# LTC_Reader_V2.net
KiCad netlist of a schematic drawn in EAGLE
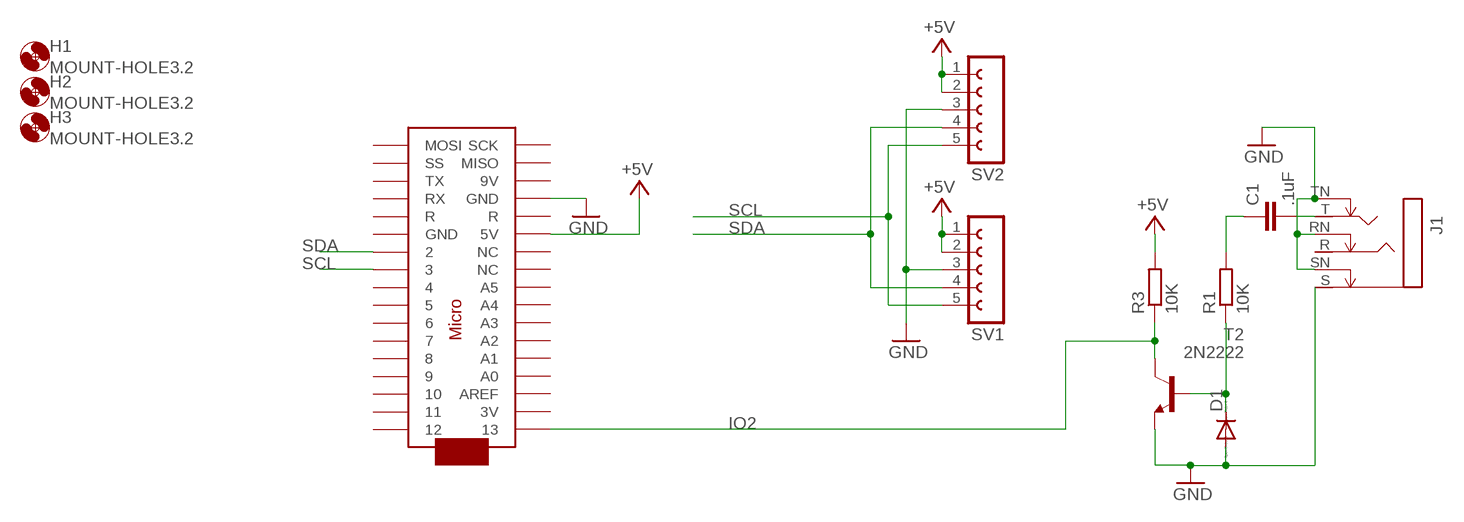
[diagram p0: schematic, sheet 1]

(export (version "E")
  (design (tool "Eeschema 10.0.6"))
  (components
    (comp (ref "C1")
      (value ".1uF")
      (footprint "eagle-import:C5B2.5")
      (libsource (lib "eagle-import") (part "C5/2.5"))
    )
    (comp (ref "D1")
      (value "1N4148DO35-7")
      (footprint "eagle-import:DO35-7")
      (libsource (lib "eagle-import") (part "1N4148DO35-7"))
    )
    (comp (ref "H1")
      (value "MOUNT-HOLE3.2")
      (footprint "eagle-import:3,2")
      (libsource (lib "eagle-import") (part "MOUNT-HOLE3.2"))
    )
    (comp (ref "H2")
      (value "MOUNT-HOLE3.2")
      (footprint "eagle-import:3,2")
      (libsource (lib "eagle-import") (part "MOUNT-HOLE3.2"))
    )
    (comp (ref "H3")
      (value "MOUNT-HOLE3.2")
      (footprint "eagle-import:3,2")
      (libsource (lib "eagle-import") (part "MOUNT-HOLE3.2"))
    )
    (comp (ref "J1")
      (value "STEREOSWS")
      (footprint "eagle-import:NMJ6HC-S")
      (libsource (lib "eagle-import") (part "STEREOSWS"))
    )
    (comp (ref "R1")
      (value "10K")
      (footprint "eagle-import:0207_10")
      (libsource (lib "eagle-import") (part "R-EU_0207/10"))
    )
    (comp (ref "R3")
      (value "10K")
      (footprint "eagle-import:0207_10")
      (libsource (lib "eagle-import") (part "R-EU_0207/10"))
    )
    (comp (ref "SV1")
      (value "FE05-1")
      (footprint "eagle-import:FE05-1")
      (libsource (lib "eagle-import") (part "FE05-1"))
    )
    (comp (ref "SV2")
      (value "FE05-1")
      (footprint "eagle-import:FE05-1")
      (libsource (lib "eagle-import") (part "FE05-1"))
    )
    (comp (ref "T2")
      (value "2N2222")
      (footprint "eagle-import:TO92-EBC-OVAL")
      (libsource (lib "eagle-import") (part "2N2222"))
    )
    (comp (ref "U$1")
      (value "ARDUINOMICRO")
      (footprint "eagle-import:ARDUINOMICRO")
      (libsource (lib "eagle-import") (part "ARDUINOMICRO"))
    )
  )
  (nets
    (net (code "1") (name "+5V") (class "Default")
      (node (ref "R3") (pin "2") (pinfunction "2_2") (pintype "passive"))
      (node (ref "SV1") (pin "1") (pinfunction "1_1") (pintype "passive"))
      (node (ref "SV1") (pin "2") (pinfunction "2_2") (pintype "passive"))
      (node (ref "SV2") (pin "1") (pinfunction "1_1") (pintype "passive"))
      (node (ref "SV2") (pin "2") (pinfunction "2_2") (pintype "passive"))
      (node (ref "U$1") (pin "P$23") (pinfunction "5V_P$23") (pintype "bidirectional"))
    )
    (net (code "2") (name "/IO2") (class "Default")
      (node (ref "R3") (pin "1") (pinfunction "1_1") (pintype "passive"))
      (node (ref "T2") (pin "C") (pinfunction "C_C") (pintype "passive"))
      (node (ref "U$1") (pin "P$34") (pinfunction "13_P$34") (pintype "bidirectional"))
    )
    (net (code "3") (name "/SCL") (class "Default")
      (node (ref "SV1") (pin "5") (pinfunction "5_5") (pintype "passive"))
      (node (ref "SV2") (pin "5") (pinfunction "5_5") (pintype "passive"))
      (node (ref "U$1") (pin "P$10") (pinfunction "3_P$10") (pintype "bidirectional"))
    )
    (net (code "4") (name "/SDA") (class "Default")
      (node (ref "SV1") (pin "4") (pinfunction "4_4") (pintype "passive"))
      (node (ref "SV2") (pin "4") (pinfunction "4_4") (pintype "passive"))
      (node (ref "U$1") (pin "P$11") (pinfunction "2_P$11") (pintype "bidirectional"))
    )
    (net (code "5") (name "GND") (class "Default")
      (node (ref "D1") (pin "A") (pinfunction "A_A") (pintype "passive"))
      (node (ref "J1") (pin "RN") (pinfunction "RN_RN") (pintype "passive"))
      (node (ref "J1") (pin "S") (pinfunction "S_S") (pintype "passive"))
      (node (ref "J1") (pin "SN") (pinfunction "SN_SN") (pintype "passive"))
      (node (ref "J1") (pin "TN") (pinfunction "TN_TN") (pintype "passive"))
      (node (ref "SV1") (pin "3") (pinfunction "3_3") (pintype "passive"))
      (node (ref "SV2") (pin "3") (pinfunction "3_3") (pintype "passive"))
      (node (ref "T2") (pin "E") (pinfunction "E_E") (pintype "passive"))
      (node (ref "U$1") (pin "P$12") (pinfunction "GND_P$12") (pintype "bidirectional"))
    )
    (net (code "6") (name "Net-(C1-Pad1)") (class "Default")
      (node (ref "C1") (pin "1") (pinfunction "1_1") (pintype "passive"))
      (node (ref "R1") (pin "2") (pinfunction "2_2") (pintype "passive"))
    )
    (net (code "7") (name "Net-(C1-Pad2)") (class "Default")
      (node (ref "C1") (pin "2") (pinfunction "2_2") (pintype "passive"))
      (node (ref "J1") (pin "T") (pinfunction "T_T") (pintype "passive"))
    )
    (net (code "8") (name "Net-(D1-PadC)") (class "Default")
      (node (ref "D1") (pin "C") (pinfunction "C_C") (pintype "passive"))
      (node (ref "R1") (pin "1") (pinfunction "1_1") (pintype "passive"))
      (node (ref "T2") (pin "B") (pinfunction "B_B") (pintype "passive"))
    )
    (net (code "9") (name "unconnected-(J1-PadR)") (class "Default")
      (node (ref "J1") (pin "R") (pinfunction "R_R") (pintype "passive"))
    )
    (net (code "10") (name "unconnected-(U$1-3V-PadP$33)") (class "Default")
      (node (ref "U$1") (pin "P$33") (pinfunction "3V_P$33") (pintype "bidirectional"))
    )
    (net (code "11") (name "unconnected-(U$1-4-PadP$9)") (class "Default")
      (node (ref "U$1") (pin "P$9") (pinfunction "4_P$9") (pintype "bidirectional"))
    )
    (net (code "12") (name "unconnected-(U$1-5-PadP$8)") (class "Default")
      (node (ref "U$1") (pin "P$8") (pinfunction "5_P$8") (pintype "bidirectional"))
    )
    (net (code "13") (name "unconnected-(U$1-6-PadP$7)") (class "Default")
      (node (ref "U$1") (pin "P$7") (pinfunction "6_P$7") (pintype "bidirectional"))
    )
    (net (code "14") (name "unconnected-(U$1-7-PadP$6)") (class "Default")
      (node (ref "U$1") (pin "P$6") (pinfunction "7_P$6") (pintype "bidirectional"))
    )
    (net (code "15") (name "unconnected-(U$1-8-PadP$5)") (class "Default")
      (node (ref "U$1") (pin "P$5") (pinfunction "8_P$5") (pintype "bidirectional"))
    )
    (net (code "16") (name "unconnected-(U$1-9-PadP$4)") (class "Default")
      (node (ref "U$1") (pin "P$4") (pinfunction "9_P$4") (pintype "bidirectional"))
    )
    (net (code "17") (name "unconnected-(U$1-9V-PadP$20)") (class "Default")
      (node (ref "U$1") (pin "P$20") (pinfunction "9V_P$20") (pintype "bidirectional"))
    )
    (net (code "18") (name "unconnected-(U$1-10-PadP$3)") (class "Default")
      (node (ref "U$1") (pin "P$3") (pinfunction "10_P$3") (pintype "bidirectional"))
    )
    (net (code "19") (name "unconnected-(U$1-11-PadP$2)") (class "Default")
      (node (ref "U$1") (pin "P$2") (pinfunction "11_P$2") (pintype "bidirectional"))
    )
    (net (code "20") (name "unconnected-(U$1-12-PadP$1)") (class "Default")
      (node (ref "U$1") (pin "P$1") (pinfunction "12_P$1") (pintype "bidirectional"))
    )
    (net (code "21") (name "unconnected-(U$1-A0-PadP$31)") (class "Default")
      (node (ref "U$1") (pin "P$31") (pinfunction "A0_P$31") (pintype "bidirectional"))
    )
    (net (code "22") (name "unconnected-(U$1-A1-PadP$30)") (class "Default")
      (node (ref "U$1") (pin "P$30") (pinfunction "A1_P$30") (pintype "bidirectional"))
    )
    (net (code "23") (name "unconnected-(U$1-A2-PadP$29)") (class "Default")
      (node (ref "U$1") (pin "P$29") (pinfunction "A2_P$29") (pintype "bidirectional"))
    )
    (net (code "24") (name "unconnected-(U$1-A3-PadP$28)") (class "Default")
      (node (ref "U$1") (pin "P$28") (pinfunction "A3_P$28") (pintype "bidirectional"))
    )
    (net (code "25") (name "unconnected-(U$1-A4-PadP$27)") (class "Default")
      (node (ref "U$1") (pin "P$27") (pinfunction "A4_P$27") (pintype "bidirectional"))
    )
    (net (code "26") (name "unconnected-(U$1-A5-PadP$26)") (class "Default")
      (node (ref "U$1") (pin "P$26") (pinfunction "A5_P$26") (pintype "bidirectional"))
    )
    (net (code "27") (name "unconnected-(U$1-AREF-PadP$32)") (class "Default")
      (node (ref "U$1") (pin "P$32") (pinfunction "AREF_P$32") (pintype "bidirectional"))
    )
    (net (code "28") (name "unconnected-(U$1-GND-PadP$21)") (class "Default")
      (node (ref "U$1") (pin "P$21") (pinfunction "GND_P$21") (pintype "bidirectional"))
    )
    (net (code "29") (name "unconnected-(U$1-MISO-PadP$19)") (class "Default")
      (node (ref "U$1") (pin "P$19") (pinfunction "MISO_P$19") (pintype "bidirectional"))
    )
    (net (code "30") (name "unconnected-(U$1-MOSI-PadP$17)") (class "Default")
      (node (ref "U$1") (pin "P$17") (pinfunction "MOSI_P$17") (pintype "bidirectional"))
    )
    (net (code "31") (name "unconnected-(U$1-NC-PadP$24)") (class "Default")
      (node (ref "U$1") (pin "P$24") (pinfunction "NC_P$24") (pintype "bidirectional"))
    )
    (net (code "32") (name "unconnected-(U$1-NC-PadP$25)") (class "Default")
      (node (ref "U$1") (pin "P$25") (pinfunction "NC_P$25") (pintype "bidirectional"))
    )
    (net (code "33") (name "unconnected-(U$1-R-PadP$13)") (class "Default")
      (node (ref "U$1") (pin "P$13") (pinfunction "R_P$13") (pintype "bidirectional"))
    )
    (net (code "34") (name "unconnected-(U$1-R-PadP$22)") (class "Default")
      (node (ref "U$1") (pin "P$22") (pinfunction "R_P$22") (pintype "bidirectional"))
    )
    (net (code "35") (name "unconnected-(U$1-RX-PadP$14)") (class "Default")
      (node (ref "U$1") (pin "P$14") (pinfunction "RX_P$14") (pintype "bidirectional"))
    )
    (net (code "36") (name "unconnected-(U$1-SCK-PadP$18)") (class "Default")
      (node (ref "U$1") (pin "P$18") (pinfunction "SCK_P$18") (pintype "bidirectional"))
    )
    (net (code "37") (name "unconnected-(U$1-SS-PadP$16)") (class "Default")
      (node (ref "U$1") (pin "P$16") (pinfunction "SS_P$16") (pintype "bidirectional"))
    )
    (net (code "38") (name "unconnected-(U$1-TX-PadP$15)") (class "Default")
      (node (ref "U$1") (pin "P$15") (pinfunction "TX_P$15") (pintype "bidirectional"))
    )
  )
)
